# E-Fuse.net
KiCad netlist of a schematic drawn in Altium Designer
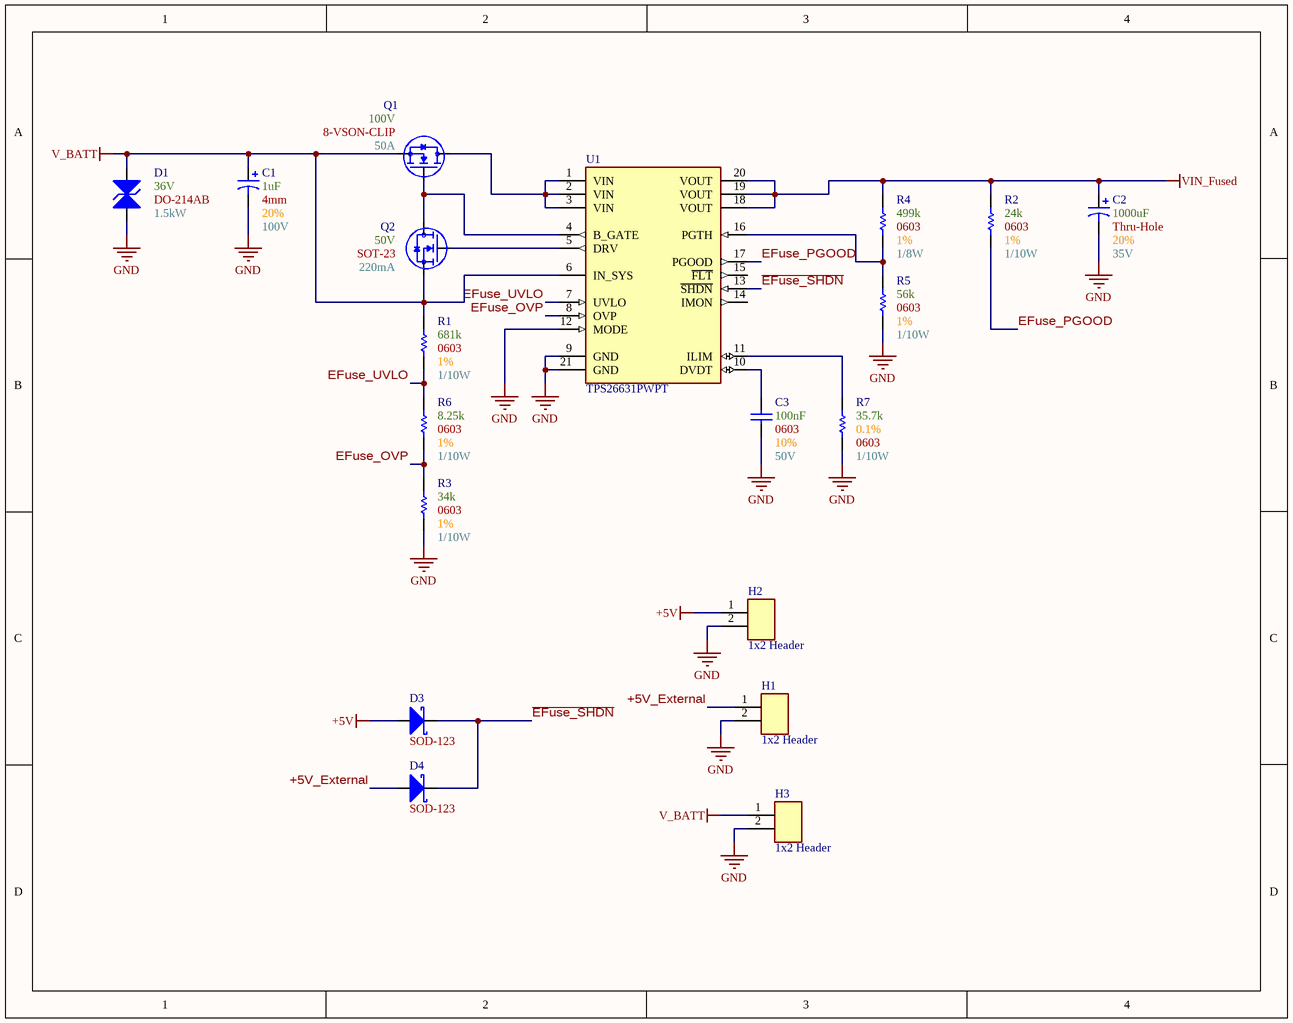
[diagram p0: E-Fuse.SchDoc]

(export (version "E")
  (design (tool "Eeschema 10.0.6"))
  (components
    (comp (ref "C1")
      (value "[Cap] 4mm 1uF 20% 100V")
      (footprint "[Cap] SMD Polarized, 4mm")
      (description "865080840001")
      (fields
        (field (name "MAX VOLTAGE") "100V")
        (field (name "SIZE PACKAGE") "4mm")
        (field (name "TOLERANCE") "20%")
        (field (name "CAPACITANCE") "1uF")
      )
      (libsource (lib "Capacitors") (part "[Cap] 4mm 1uF 20% 100V"))
    )
    (comp (ref "C2")
      (value "[Cap] Thru-Hole 1000uF 20% 35V")
      (footprint "[Cap] Thru-Hole Polarized 10mm")
      (description "35PK1000MEFC10X20")
      (fields
        (field (name "MAX VOLTAGE") "35V")
        (field (name "SIZE PACKAGE") "Thru-Hole")
        (field (name "TOLERANCE") "20%")
        (field (name "CAPACITANCE") "1000uF")
      )
      (libsource (lib "Capacitors") (part "[Cap] Thru-Hole 1000uF 20% 35V"))
    )
    (comp (ref "C3")
      (value "[Cap] 0603 0.1uF 10% 50V")
      (footprint "[Cap] SMD 0603")
      (description "CL10B104KB8NNNC")
      (fields
        (field (name "MAX VOLTAGE") "50V")
        (field (name "SIZE PACKAGE") "0603")
        (field (name "TOLERANCE") "10%")
        (field (name "CAPACITANCE") "100nF")
      )
      (libsource (lib "Capacitors") (part "[Cap] 0603 0.1uF 10% 50V"))
    )
    (comp (ref "D1")
      (value "DO-214AB")
      (footprint "DO-214AB")
      (description "SMCJ36CA")
      (fields (field (name "WATTAGE") "1.5kW") (field (name "OPTIMAL ZENER VOLTAGE") "36V"))
      (libsource (lib "Diodes") (part "[TVS] 36Vnom 40Vclamp_max"))
    )
    (comp (ref "D3")
      (value "SOD123")
      (footprint "SOD-123")
      (description "B5819W-TP")
      (libsource (lib "Diodes") (part "[Schottky] SMD 40V 1A"))
    )
    (comp (ref "D4")
      (value "SOD123")
      (footprint "SOD-123")
      (description "B5819W-TP")
      (libsource (lib "Diodes") (part "[Schottky] SMD 40V 1A"))
    )
    (comp (ref "H1")
      (value "1x2 Header")
      (footprint "[Header] 1x2 Male")
      (description "2.54mm pitch")
      (libsource (lib "Connectors") (part "[Header] 1x2 Male"))
    )
    (comp (ref "H2")
      (value "1x2 Header")
      (footprint "[Header] 1x2 Male")
      (description "2.54mm pitch")
      (libsource (lib "Connectors") (part "[Header] 1x2 Male"))
    )
    (comp (ref "H3")
      (value "1x2 Header")
      (footprint "[Header] 1x2 Male")
      (description "2.54mm pitch")
      (libsource (lib "Connectors") (part "[Header] 1x2 Male"))
    )
    (comp (ref "Q1")
      (value "CSD19537Q3")
      (footprint "8-VSON-CLIP")
      (fields
        (field (name "IDS_MAX") "50A")
        (field (name "PACKAGE") "8-VSON-CLIP")
        (field (name "VDS_MAX") "100V")
      )
      (libsource (lib "Transistors") (part "[NMOS] SMD 100V 50A 14.5mOhm"))
    )
    (comp (ref "Q2")
      (value "[NMOS] SMD 50V 220mA 3mOhm")
      (footprint "SOT-23")
      (description "BSS138")
      (fields
        (field (name "IDS_MAX") "220mA")
        (field (name "PACKAGE") "SOT-23")
        (field (name "VDS_MAX") "50V")
      )
      (libsource (lib "Transistors") (part "[NMOS] SMD 50V 220mA 3mOhm"))
    )
    (comp (ref "R1")
      (value "[681k] SMD 0603 1% 1/10W")
      (footprint "[Res] SMD 0603")
      (description "RT0603FRE07681KL")
      (fields
        (field (name "WATTAGE") "1/10W")
        (field (name "TOLERANCE") "1%")
        (field (name "RESISTANCE") "681k")
        (field (name "SIZE PACKAGE") "0603")
      )
      (libsource (lib "Resistors") (part "[681k] SMD 0603 1% 1/10W"))
    )
    (comp (ref "R2")
      (value "[24k] SMD 0603 1% 1/10W")
      (footprint "[Res] SMD 0603")
      (description "RC0603FR-1324KL")
      (fields
        (field (name "WATTAGE") "1/10W")
        (field (name "TOLERANCE") "1%")
        (field (name "RESISTANCE") "24k")
        (field (name "SIZE PACKAGE") "0603")
      )
      (libsource (lib "Resistors") (part "[24k] SMD 0603 1% 1/10W"))
    )
    (comp (ref "R3")
      (value "[34k] SMD 0603 1% 1/10W")
      (footprint "[Res] SMD 0603")
      (description "RC0603FR-1334KL")
      (fields
        (field (name "WATTAGE") "1/10W")
        (field (name "TOLERANCE") "1%")
        (field (name "RESISTANCE") "34k")
        (field (name "SIZE PACKAGE") "0603")
      )
      (libsource (lib "Resistors") (part "[34k] SMD 0603 1% 1/10W"))
    )
    (comp (ref "R4")
      (value "[499k] SMD 0603 1% 1/8W")
      (footprint "[Res] SMD 0603")
      (description "CRCW0603499KFKEA")
      (fields
        (field (name "WATTAGE") "1/8W")
        (field (name "TOLERANCE") "1%")
        (field (name "RESISTANCE") "499k")
        (field (name "SIZE PACKAGE") "0603")
      )
      (libsource (lib "Resistors") (part "[499k] SMD 0603 1% 1/8W"))
    )
    (comp (ref "R5")
      (value "[56k] SMD 0603 1% 1/10W")
      (footprint "[Res] SMD 0603")
      (description "CRGCQ0603F56K")
      (fields
        (field (name "WATTAGE") "1/10W")
        (field (name "TOLERANCE") "1%")
        (field (name "RESISTANCE") "56k")
        (field (name "SIZE PACKAGE") "0603")
      )
      (libsource (lib "Resistors") (part "[56k] SMD 0603 1% 1/10W"))
    )
    (comp (ref "R6")
      (value "[8.25k] SMD 0603 1% 1/10W")
      (footprint "[Res] SMD 0603")
      (description "AF0603FR-078K25L")
      (fields
        (field (name "WATTAGE") "1/10W")
        (field (name "TOLERANCE") "1%")
        (field (name "RESISTANCE") "8.25k")
        (field (name "SIZE PACKAGE") "0603")
      )
      (libsource (lib "Resistors") (part "[8.25k] SMD 0603 1% 1/10W"))
    )
    (comp (ref "R7")
      (value "[35.7k] SMD 0603 0.1% 1/10W")
      (footprint "[Res] SMD 0603")
      (description "RT0603BRE0735K7L")
      (fields
        (field (name "WATTAGE") "1/10W")
        (field (name "TOLERANCE") "0.1%")
        (field (name "RESISTANCE") "35.7k")
        (field (name "SIZE PACKAGE") "0603")
      )
      (libsource (lib "Resistors") (part "[35.7k] SMD 0603 0.1% 1/10W"))
    )
    (comp (ref "U1")
      (value "TPS26631PWPT")
      (footprint "[E-Fuse] 4.5-60V 6A")
      (libsource (lib "ICs") (part "[E-Fuse] 4.5-60V 6A"))
    )
  )
  (nets
    (net (code "1") (name "+5V") (class "Default")
      (node (ref "D3") (pin "2") (pinfunction "A_2") (pintype "passive"))
      (node (ref "H2") (pin "1") (pintype "passive"))
    )
    (net (code "2") (name "/+5V_External") (class "Default")
      (node (ref "D4") (pin "2") (pinfunction "A_2") (pintype "passive"))
      (node (ref "H1") (pin "1") (pintype "passive"))
    )
    (net (code "3") (name "/EFuse_OVP") (class "Default")
      (node (ref "R3") (pin "2") (pinfunction "2_2") (pintype "passive"))
      (node (ref "R6") (pin "1") (pinfunction "1_1") (pintype "passive"))
      (node (ref "U1") (pin "8") (pinfunction "OVP_8") (pintype "input"))
    )
    (net (code "4") (name "/EFuse_PGOOD") (class "Default")
      (node (ref "R2") (pin "1") (pinfunction "1_1") (pintype "passive"))
      (node (ref "U1") (pin "17") (pinfunction "PGOOD_17") (pintype "output"))
    )
    (net (code "5") (name "/EFuse_SHDN") (class "Default")
      (node (ref "D3") (pin "1") (pinfunction "K_1") (pintype "passive"))
      (node (ref "D4") (pin "1") (pinfunction "K_1") (pintype "passive"))
      (node (ref "U1") (pin "13") (pinfunction "~{SHDN}_13") (pintype "input"))
    )
    (net (code "6") (name "/EFuse_UVLO") (class "Default")
      (node (ref "R1") (pin "1") (pinfunction "1_1") (pintype "passive"))
      (node (ref "R6") (pin "2") (pinfunction "2_2") (pintype "passive"))
      (node (ref "U1") (pin "7") (pinfunction "UVLO_7") (pintype "input"))
    )
    (net (code "7") (name "GND") (class "Default")
      (node (ref "C1") (pin "2") (pinfunction "2_2") (pintype "passive"))
      (node (ref "C2") (pin "2") (pinfunction "2_2") (pintype "passive"))
      (node (ref "C3") (pin "1") (pinfunction "1_1") (pintype "passive"))
      (node (ref "D1") (pin "2") (pinfunction "A_2") (pintype "passive"))
      (node (ref "H1") (pin "2") (pintype "passive"))
      (node (ref "H2") (pin "2") (pintype "passive"))
      (node (ref "H3") (pin "2") (pintype "passive"))
      (node (ref "R3") (pin "1") (pinfunction "1_1") (pintype "passive"))
      (node (ref "R5") (pin "1") (pinfunction "1_1") (pintype "passive"))
      (node (ref "R7") (pin "1") (pinfunction "1_1") (pintype "passive"))
      (node (ref "U1") (pin "12") (pinfunction "MODE_12") (pintype "input"))
      (node (ref "U1") (pin "21") (pinfunction "GND_21") (pintype "power_in"))
      (node (ref "U1") (pin "9") (pinfunction "GND_9") (pintype "passive"))
    )
    (net (code "8") (name "Net-(Q1-Drain)") (class "Default")
      (node (ref "Q1") (pin "3") (pinfunction "Drain_3") (pintype "passive"))
      (node (ref "U1") (pin "1") (pinfunction "VIN_1") (pintype "passive"))
      (node (ref "U1") (pin "2") (pinfunction "VIN_2") (pintype "passive"))
      (node (ref "U1") (pin "3") (pinfunction "VIN_3") (pintype "passive"))
    )
    (net (code "9") (name "Net-(Q1-Gate)") (class "Default")
      (node (ref "Q1") (pin "1") (pinfunction "Gate_1") (pintype "passive"))
      (node (ref "Q2") (pin "3") (pinfunction "Drain_3") (pintype "passive"))
      (node (ref "U1") (pin "4") (pinfunction "B_GATE_4") (pintype "output"))
    )
    (net (code "10") (name "Net-(Q2-Gate)") (class "Default")
      (node (ref "Q2") (pin "1") (pinfunction "Gate_1") (pintype "passive"))
      (node (ref "U1") (pin "5") (pinfunction "DRV_5") (pintype "output"))
    )
    (net (code "11") (name "Net-(U1-DVDT)") (class "Default")
      (node (ref "C3") (pin "2") (pinfunction "2_2") (pintype "passive"))
      (node (ref "U1") (pin "10") (pinfunction "DVDT_10") (pintype "bidirectional"))
    )
    (net (code "12") (name "Net-(U1-ILIM)") (class "Default")
      (node (ref "R7") (pin "2") (pinfunction "2_2") (pintype "passive"))
      (node (ref "U1") (pin "11") (pinfunction "ILIM_11") (pintype "bidirectional"))
    )
    (net (code "13") (name "Net-(U1-PGTH)") (class "Default")
      (node (ref "R4") (pin "1") (pinfunction "1_1") (pintype "passive"))
      (node (ref "R5") (pin "2") (pinfunction "2_2") (pintype "passive"))
      (node (ref "U1") (pin "16") (pinfunction "PGTH_16") (pintype "input"))
    )
    (net (code "14") (name "VIN_Fused") (class "Default")
      (node (ref "C2") (pin "1") (pinfunction "1_1") (pintype "passive"))
      (node (ref "R2") (pin "2") (pinfunction "2_2") (pintype "passive"))
      (node (ref "R4") (pin "2") (pinfunction "2_2") (pintype "passive"))
      (node (ref "U1") (pin "18") (pinfunction "VOUT_18") (pintype "passive"))
      (node (ref "U1") (pin "19") (pinfunction "VOUT_19") (pintype "passive"))
      (node (ref "U1") (pin "20") (pinfunction "VOUT_20") (pintype "passive"))
    )
    (net (code "15") (name "V_BATT") (class "Default")
      (node (ref "C1") (pin "1") (pinfunction "1_1") (pintype "passive"))
      (node (ref "D1") (pin "1") (pinfunction "K_1") (pintype "passive"))
      (node (ref "H3") (pin "1") (pintype "passive"))
      (node (ref "Q1") (pin "2") (pinfunction "Source_2") (pintype "passive"))
      (node (ref "Q2") (pin "2") (pinfunction "Source_2") (pintype "passive"))
      (node (ref "R1") (pin "2") (pinfunction "2_2") (pintype "passive"))
      (node (ref "U1") (pin "6") (pinfunction "IN_SYS_6") (pintype "power_in"))
    )
    (net (code "16") (name "unconnected-(U1-IMON-Pad14)") (class "Default")
      (node (ref "U1") (pin "14") (pinfunction "IMON_14") (pintype "output"))
    )
    (net (code "17") (name "unconnected-(U1-~{FLT}-Pad15)") (class "Default")
      (node (ref "U1") (pin "15") (pinfunction "~{FLT}_15") (pintype "output"))
    )
  )
)
